# DCDC-BASE-X2.net
KiCad netlist of a schematic drawn in EAGLE
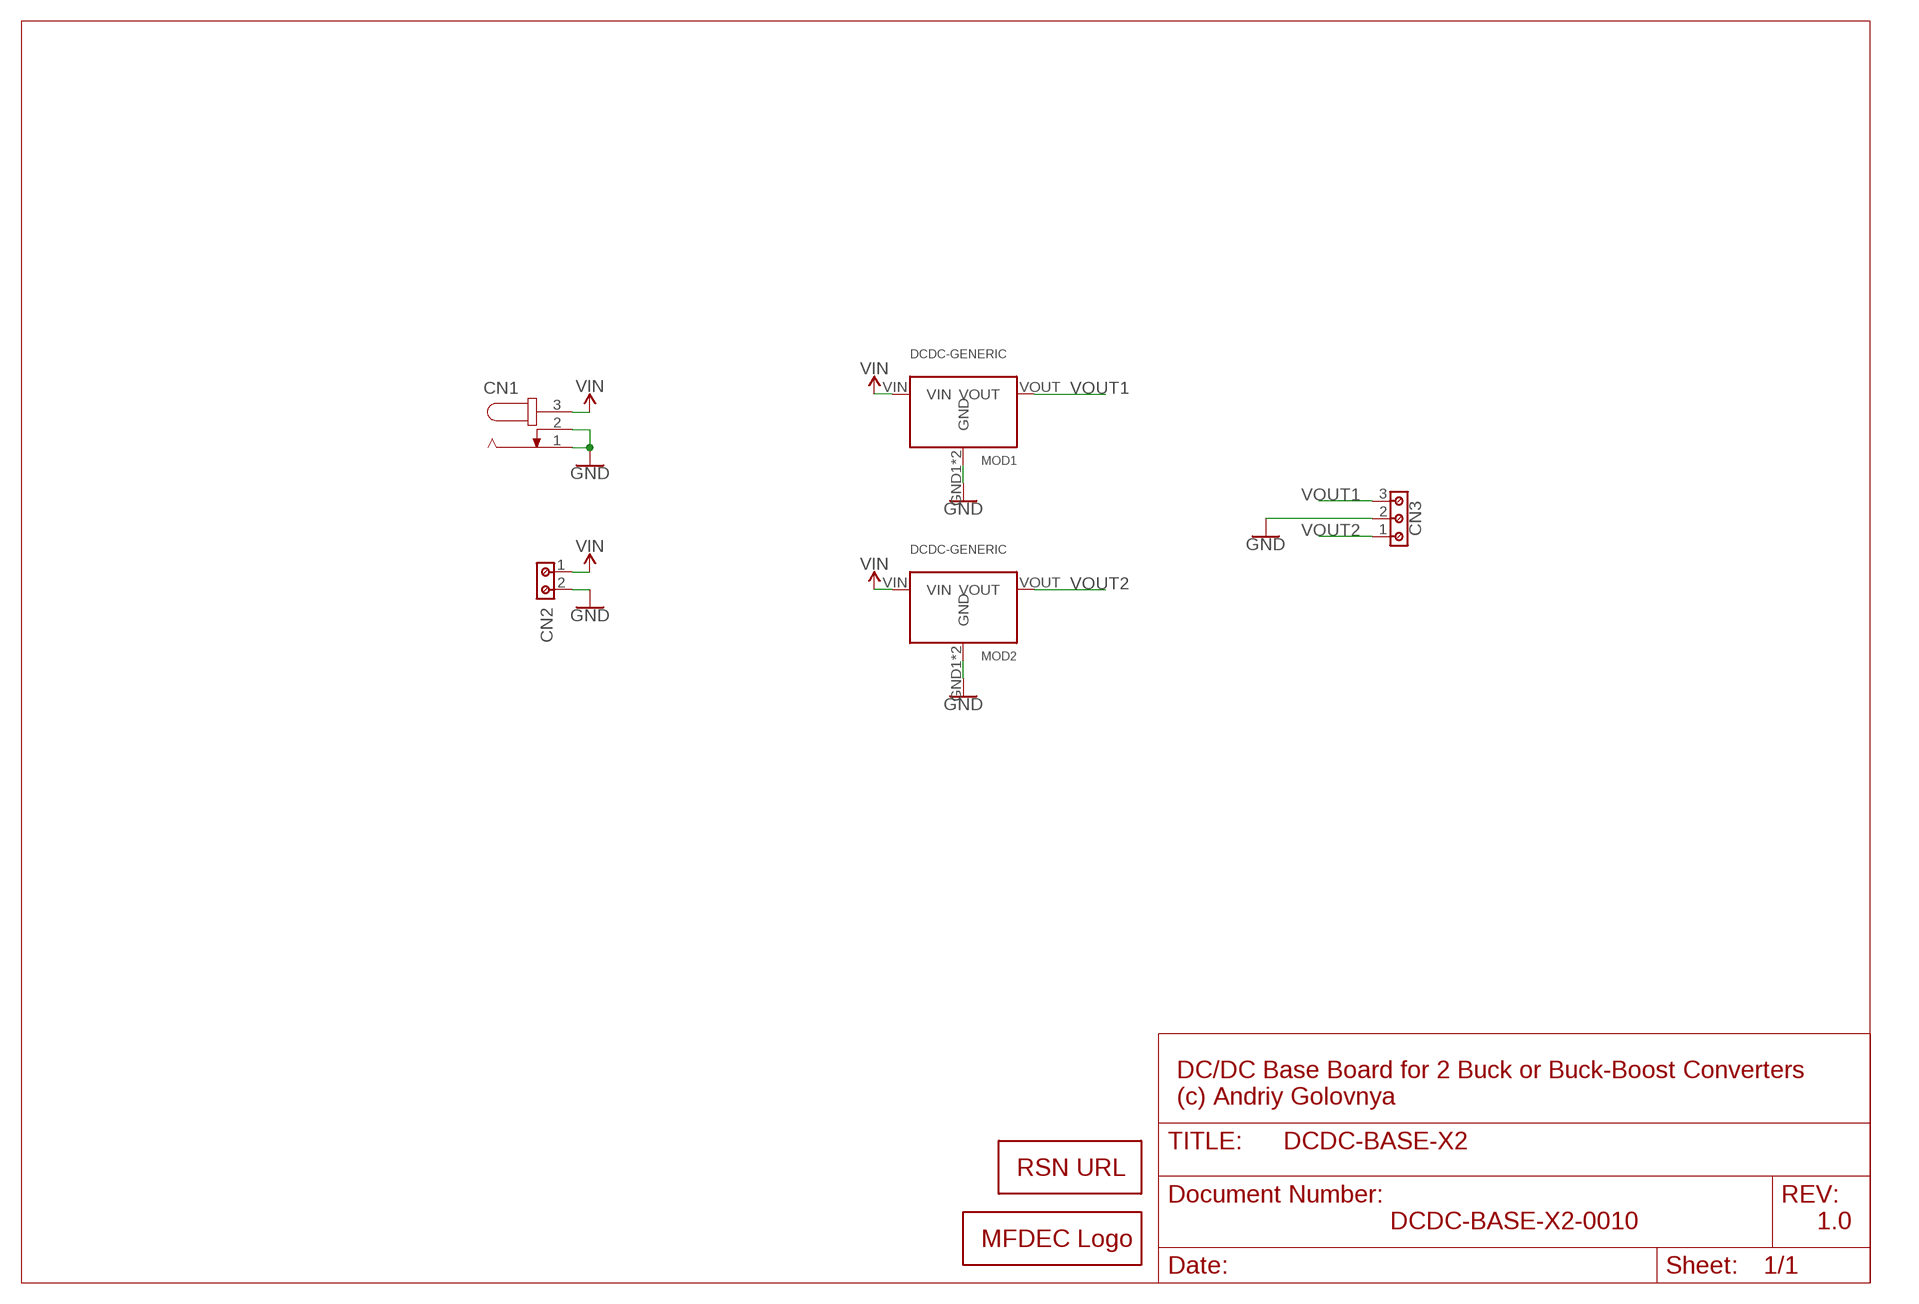
[diagram p0: schematic, sheet 1]

(export (version "E")
  (design (tool "Eeschema 10.0.6"))
  (components
    (comp (ref "CN1")
      (value "JACK-PLUG1")
      (footprint "eagle-import:SPC4078")
      (libsource (lib "eagle-import") (part "JACK-PLUG1"))
    )
    (comp (ref "CN2")
      (value "691213510002")
      (footprint "eagle-import:691213510002")
      (libsource (lib "eagle-import") (part "691213510002"))
    )
    (comp (ref "CN3")
      (value "691213510003")
      (footprint "eagle-import:691213510003")
      (libsource (lib "eagle-import") (part "691213510003"))
    )
    (comp (ref "LOGO1")
      (value "RSNURL_QR_8MM")
      (footprint "eagle-import:RSNURL_QR_8MM")
      (libsource (lib "eagle-import") (part "RSNURL_QR_8MM"))
    )
    (comp (ref "LOGO2")
      (value "MFDECLOGO_L_10MM")
      (footprint "eagle-import:MFDEC_L_10MM")
      (libsource (lib "eagle-import") (part "MFDECLOGO_L_10MM"))
    )
    (comp (ref "MOD1")
      (value "DCDC-GENERIC")
      (footprint "eagle-import:DCDC-BOARD")
      (libsource (lib "eagle-import") (part "DCDC-GENERIC"))
    )
    (comp (ref "MOD2")
      (value "DCDC-GENERIC")
      (footprint "eagle-import:DCDC-BOARD")
      (libsource (lib "eagle-import") (part "DCDC-GENERIC"))
    )
  )
  (nets
    (net (code "1") (name "/VOUT1") (class "Default")
      (node (ref "CN3") (pin "3") (pinfunction "3_3") (pintype "passive"))
      (node (ref "MOD1") (pin "VOUT") (pinfunction "VOUT_VOUT") (pintype "bidirectional"))
    )
    (net (code "2") (name "/VOUT2") (class "Default")
      (node (ref "CN3") (pin "1") (pinfunction "1_1") (pintype "passive"))
      (node (ref "MOD2") (pin "VOUT") (pinfunction "VOUT_VOUT") (pintype "bidirectional"))
    )
    (net (code "3") (name "GND") (class "Default")
      (node (ref "CN1") (pin "1") (pinfunction "1_1") (pintype "passive"))
      (node (ref "CN1") (pin "2") (pinfunction "2_2") (pintype "passive"))
      (node (ref "CN2") (pin "2") (pinfunction "2_2") (pintype "passive"))
      (node (ref "CN3") (pin "2") (pinfunction "2_2") (pintype "passive"))
      (node (ref "MOD1") (pin "GND1") (pinfunction "GND_GND1") (pintype "bidirectional"))
      (node (ref "MOD1") (pin "GND2") (pinfunction "GND_GND2") (pintype "bidirectional"))
      (node (ref "MOD2") (pin "GND1") (pinfunction "GND_GND1") (pintype "bidirectional"))
      (node (ref "MOD2") (pin "GND2") (pinfunction "GND_GND2") (pintype "bidirectional"))
    )
    (net (code "4") (name "VIN") (class "Default")
      (node (ref "CN1") (pin "3") (pinfunction "3_3") (pintype "passive"))
      (node (ref "CN2") (pin "1") (pinfunction "1_1") (pintype "passive"))
      (node (ref "MOD1") (pin "VIN") (pinfunction "VIN_VIN") (pintype "bidirectional"))
      (node (ref "MOD2") (pin "VIN") (pinfunction "VIN_VIN") (pintype "bidirectional"))
    )
  )
)
